# Speedometer_PCB_schematic.net
KiCad netlist of a schematic drawn in Altium Designer
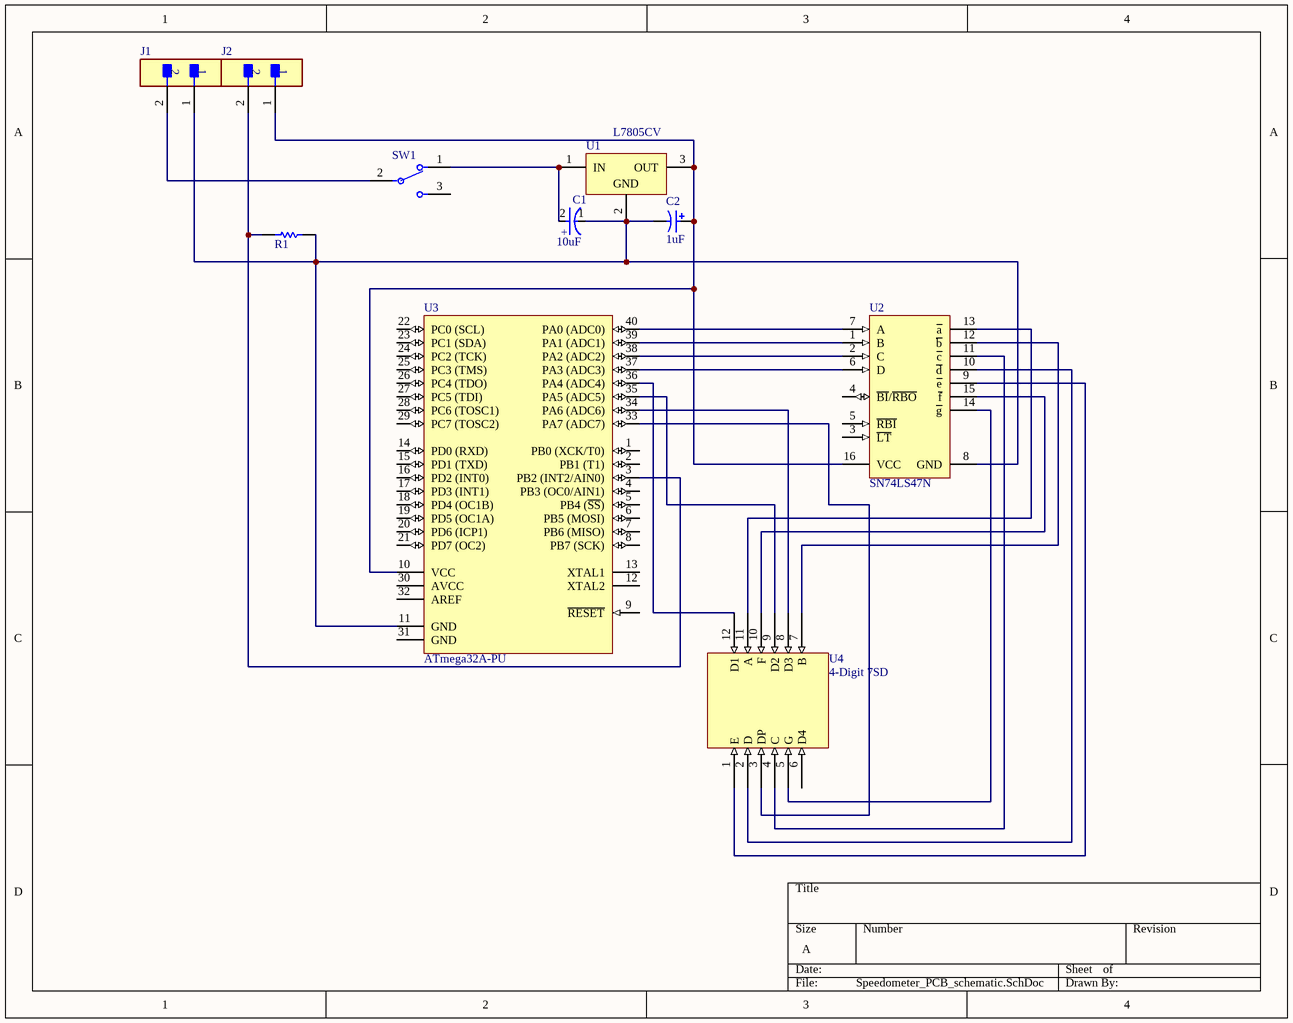
[diagram p0: Speedometer_PCB_schematic.SchDoc]

(export (version "E")
  (design (tool "Eeschema 10.0.6"))
  (components
    (comp (ref "C1")
      (value "ECA2AM100")
      (footprint "FP-RAD-TH-D_5_0_5-L_11_1-MFG")
      (description "Aluminum Electrolytic Capacitors (Radial Lead Type) 10uF ±20% 100V")
      (fields
        (field (name "CAPACITANCE") "10uF")
        (field (name "VOLTAGE") "100V")
        (field (name "TOLERANCE") "20%")
      )
      (libsource (lib "Altium Content Vault") (part "a00bbbee19879c290e62620ae7e47b1"))
    )
    (comp (ref "C2")
      (value "1uF")
      (footprint "CAPPR55-200-1100X500X1200")
      (description "Aluminum Electrolytic Capacitor, 1 uF, +/- 20%, 50 V, -55 to 105 degC, 2-Pin THD, RoHS, Bulk")
      (libsource (lib "Altium Content Vault") (part "CAP-P-2"))
    )
    (comp (ref "J1")
      (value "M20-9990246")
      (footprint "FP-M20-9990246-MFG")
      (description "Connector Header Through Hole 2 position 0.100\" (2.54mm)")
      (fields (field (name "OCTOPART") "https://octopart.com/m20-9990246-harwin-2590635"))
      (libsource (lib "Altium Content Vault") (part "3bc925449376181038e59eaffc5286c"))
    )
    (comp (ref "J2")
      (value "M20-9990246")
      (footprint "FP-M20-9990246-MFG")
      (description "Connector Header Through Hole 2 position 0.100\" (2.54mm)")
      (fields (field (name "OCTOPART") "https://octopart.com/m20-9990246-harwin-2590635"))
      (libsource (lib "Altium Content Vault") (part "3bc925449376181038e59eaffc5286c"))
    )
    (comp (ref "R1")
      (value "MFR-25FBF52-1K")
      (footprint "RESA60-630X240")
      (description "Axial Resistor, 1 KOhm, +/- 1%, 250 mW, -55 to 155 degC, 2-Pin THD, RoHS, Bulk")
      (fields (field (name "TOLERANCE") "1%"))
      (libsource (lib "Altium Content Vault") (part "RES-2"))
    )
    (comp (ref "SW1")
      (value "1101M2S3CQE2")
      (footprint "FP-1101M2S3CQE2-MFG")
      (description "SWITCH SLIDE SPDT 6A 120V")
      (libsource (lib "Altium Content Vault") (part "7fcaa069a19c2acd609832313418d7c"))
    )
    (comp (ref "U1")
      (value "L7805CV")
      (footprint "TO220")
      (description "Positive Voltage Regulator, 5V, 3-Pin TO-220")
      (libsource (lib "Altium Content Vault") (part "PM-REG-L4940-SIL3"))
    )
    (comp (ref "U2")
      (value "SN74LS47N")
      (footprint "N0016A")
      (description "BCD-to-7-Segment Decoder / Driver, 4.75 to 5.25 V, 0 to 70 degC, 16-pin DIP (N16), Pb-Free (RoHS)")
      (fields (field (name "MANUFACTURER") "Texas Instruments"))
      (libsource (lib "Altium Content Vault") (part "TI-SNX4XX247-16"))
    )
    (comp (ref "U3")
      (value "ATmega32A-PU")
      (footprint "40P6")
      (libsource (lib "Altium Content Vault") (part "MC-8B-AT16A-IL40"))
    )
    (comp (ref "U4")
      (value "4-Digit 7SD")
      (footprint "4-Digit 7SD")
      (libsource (lib "Speedometer") (part "4-Digit 7SD"))
    )
  )
  (nets
    (net (code "1") (name "Net-(C1-A)") (class "Default")
      (node (ref "C1") (pin "2") (pinfunction "A_2") (pintype "passive"))
      (node (ref "SW1") (pin "1") (pinfunction "1_1") (pintype "passive"))
      (node (ref "U1") (pin "1") (pinfunction "IN_1") (pintype "power_in"))
    )
    (net (code "2") (name "Net-(C1-C)") (class "Default")
      (node (ref "C1") (pin "1") (pinfunction "C_1") (pintype "passive"))
      (node (ref "C2") (pin "2") (pinfunction "2_2") (pintype "passive"))
      (node (ref "J1") (pin "1") (pinfunction "1_1") (pintype "passive"))
      (node (ref "R1") (pin "2") (pinfunction "2_2") (pintype "passive"))
      (node (ref "U1") (pin "2") (pinfunction "GND_2") (pintype "power_in"))
      (node (ref "U2") (pin "8") (pinfunction "GND_8") (pintype "power_in"))
      (node (ref "U3") (pin "11") (pinfunction "GND_11") (pintype "power_in"))
    )
    (net (code "3") (name "Net-(SW1-COMM)") (class "Default")
      (node (ref "J1") (pin "2") (pinfunction "2_2") (pintype "passive"))
      (node (ref "SW1") (pin "2") (pinfunction "COMM_2") (pintype "passive"))
    )
    (net (code "4") (name "Net-(U1-OUT)") (class "Default")
      (node (ref "C2") (pin "1") (pinfunction "1_1") (pintype "passive"))
      (node (ref "J2") (pin "1") (pinfunction "1_1") (pintype "passive"))
      (node (ref "U1") (pin "3") (pinfunction "OUT_3") (pintype "power_in"))
      (node (ref "U2") (pin "16") (pinfunction "VCC_16") (pintype "power_in"))
      (node (ref "U3") (pin "10") (pinfunction "VCC_10") (pintype "power_in"))
    )
    (net (code "5") (name "Net-(U2-A)") (class "Default")
      (node (ref "U2") (pin "7") (pinfunction "A_7") (pintype "input"))
      (node (ref "U3") (pin "40") (pinfunction "PA0_(ADC0)_40") (pintype "bidirectional"))
    )
    (net (code "6") (name "Net-(U2-B)") (class "Default")
      (node (ref "U2") (pin "1") (pinfunction "B_1") (pintype "input"))
      (node (ref "U3") (pin "39") (pinfunction "PA1_(ADC1)_39") (pintype "bidirectional"))
    )
    (net (code "7") (name "Net-(U2-C)") (class "Default")
      (node (ref "U2") (pin "2") (pinfunction "C_2") (pintype "input"))
      (node (ref "U3") (pin "38") (pinfunction "PA2_(ADC2)_38") (pintype "bidirectional"))
    )
    (net (code "8") (name "Net-(U2-D)") (class "Default")
      (node (ref "U2") (pin "6") (pinfunction "D_6") (pintype "input"))
      (node (ref "U3") (pin "37") (pinfunction "PA3_(ADC3)_37") (pintype "bidirectional"))
    )
    (net (code "9") (name "Net-(U2-~{a})") (class "Default")
      (node (ref "U2") (pin "13") (pinfunction "~{a}_13") (pintype "open_collector"))
      (node (ref "U4") (pin "11") (pinfunction "A_11") (pintype "input"))
    )
    (net (code "10") (name "Net-(U2-~{b})") (class "Default")
      (node (ref "U2") (pin "12") (pinfunction "~{b}_12") (pintype "open_collector"))
      (node (ref "U4") (pin "7") (pinfunction "B_7") (pintype "input"))
    )
    (net (code "11") (name "Net-(U2-~{c})") (class "Default")
      (node (ref "U2") (pin "11") (pinfunction "~{c}_11") (pintype "open_collector"))
      (node (ref "U4") (pin "4") (pinfunction "C_4") (pintype "input"))
    )
    (net (code "12") (name "Net-(U2-~{d})") (class "Default")
      (node (ref "U2") (pin "10") (pinfunction "~{d}_10") (pintype "open_collector"))
      (node (ref "U4") (pin "2") (pinfunction "D_2") (pintype "input"))
    )
    (net (code "13") (name "Net-(U2-~{e})") (class "Default")
      (node (ref "U2") (pin "9") (pinfunction "~{e}_9") (pintype "open_collector"))
      (node (ref "U4") (pin "1") (pinfunction "E_1") (pintype "input"))
    )
    (net (code "14") (name "Net-(U2-~{f})") (class "Default")
      (node (ref "U2") (pin "15") (pinfunction "~{f}_15") (pintype "open_collector"))
      (node (ref "U4") (pin "10") (pinfunction "F_10") (pintype "input"))
    )
    (net (code "15") (name "Net-(U2-~{g})") (class "Default")
      (node (ref "U2") (pin "14") (pinfunction "~{g}_14") (pintype "open_collector"))
      (node (ref "U4") (pin "5") (pinfunction "G_5") (pintype "input"))
    )
    (net (code "16") (name "Net-(U3-PA4_(ADC4))") (class "Default")
      (node (ref "U3") (pin "36") (pinfunction "PA4_(ADC4)_36") (pintype "bidirectional"))
      (node (ref "U4") (pin "12") (pinfunction "D1_12") (pintype "input"))
    )
    (net (code "17") (name "Net-(U3-PA5_(ADC5))") (class "Default")
      (node (ref "U3") (pin "35") (pinfunction "PA5_(ADC5)_35") (pintype "bidirectional"))
      (node (ref "U4") (pin "9") (pinfunction "D2_9") (pintype "input"))
    )
    (net (code "18") (name "Net-(U3-PA6_(ADC6))") (class "Default")
      (node (ref "U3") (pin "34") (pinfunction "PA6_(ADC6)_34") (pintype "bidirectional"))
      (node (ref "U4") (pin "8") (pinfunction "D3_8") (pintype "input"))
    )
    (net (code "19") (name "Net-(U3-PA7_(ADC7))") (class "Default")
      (node (ref "U3") (pin "33") (pinfunction "PA7_(ADC7)_33") (pintype "bidirectional"))
      (node (ref "U4") (pin "3") (pinfunction "DP_3") (pintype "input"))
    )
    (net (code "20") (name "Net-(U3-PB2_(INT2{slash}AIN0))") (class "Default")
      (node (ref "J2") (pin "2") (pinfunction "2_2") (pintype "passive"))
      (node (ref "R1") (pin "1") (pinfunction "1_1") (pintype "passive"))
      (node (ref "U3") (pin "3") (pinfunction "PB2_(INT2/AIN0)_3") (pintype "bidirectional"))
    )
    (net (code "21") (name "unconnected-(SW1-Pad3)") (class "Default")
      (node (ref "SW1") (pin "3") (pinfunction "3_3") (pintype "passive"))
    )
    (net (code "22") (name "unconnected-(U2-~{BI}{slash}~{RBO}-Pad4)") (class "Default")
      (node (ref "U2") (pin "4") (pinfunction "~{BI}/~{RBO}_4") (pintype "bidirectional"))
    )
    (net (code "23") (name "unconnected-(U2-~{LT}-Pad3)") (class "Default")
      (node (ref "U2") (pin "3") (pinfunction "~{LT}_3") (pintype "input"))
    )
    (net (code "24") (name "unconnected-(U2-~{RBI}-Pad5)") (class "Default")
      (node (ref "U2") (pin "5") (pinfunction "~{RBI}_5") (pintype "input"))
    )
    (net (code "25") (name "unconnected-(U3-AREF-Pad32)") (class "Default")
      (node (ref "U3") (pin "32") (pinfunction "AREF_32") (pintype "power_in"))
    )
    (net (code "26") (name "unconnected-(U3-AVCC-Pad30)") (class "Default")
      (node (ref "U3") (pin "30") (pinfunction "AVCC_30") (pintype "power_in"))
    )
    (net (code "27") (name "unconnected-(U3-GND-Pad31)") (class "Default")
      (node (ref "U3") (pin "31") (pinfunction "GND_31") (pintype "power_in"))
    )
    (net (code "28") (name "unconnected-(U3-PB0_(XCK{slash}T0)-Pad1)") (class "Default")
      (node (ref "U3") (pin "1") (pinfunction "PB0_(XCK/T0)_1") (pintype "bidirectional"))
    )
    (net (code "29") (name "unconnected-(U3-PB1_(T1)-Pad2)") (class "Default")
      (node (ref "U3") (pin "2") (pinfunction "PB1_(T1)_2") (pintype "bidirectional"))
    )
    (net (code "30") (name "unconnected-(U3-PB3_(OC0{slash}AIN1)-Pad4)") (class "Default")
      (node (ref "U3") (pin "4") (pinfunction "PB3_(OC0/AIN1)_4") (pintype "bidirectional"))
    )
    (net (code "31") (name "unconnected-(U3-PB4_(~{SS})-Pad5)") (class "Default")
      (node (ref "U3") (pin "5") (pinfunction "PB4_(~{SS})_5") (pintype "bidirectional"))
    )
    (net (code "32") (name "unconnected-(U3-PB5_(MOSI)-Pad6)") (class "Default")
      (node (ref "U3") (pin "6") (pinfunction "PB5_(MOSI)_6") (pintype "bidirectional"))
    )
    (net (code "33") (name "unconnected-(U3-PB6_(MISO)-Pad7)") (class "Default")
      (node (ref "U3") (pin "7") (pinfunction "PB6_(MISO)_7") (pintype "bidirectional"))
    )
    (net (code "34") (name "unconnected-(U3-PB7_(SCK)-Pad8)") (class "Default")
      (node (ref "U3") (pin "8") (pinfunction "PB7_(SCK)_8") (pintype "bidirectional"))
    )
    (net (code "35") (name "unconnected-(U3-PC0_(SCL)-Pad22)") (class "Default")
      (node (ref "U3") (pin "22") (pinfunction "PC0_(SCL)_22") (pintype "bidirectional"))
    )
    (net (code "36") (name "unconnected-(U3-PC1_(SDA)-Pad23)") (class "Default")
      (node (ref "U3") (pin "23") (pinfunction "PC1_(SDA)_23") (pintype "bidirectional"))
    )
    (net (code "37") (name "unconnected-(U3-PC2_(TCK)-Pad24)") (class "Default")
      (node (ref "U3") (pin "24") (pinfunction "PC2_(TCK)_24") (pintype "bidirectional"))
    )
    (net (code "38") (name "unconnected-(U3-PC3_(TMS)-Pad25)") (class "Default")
      (node (ref "U3") (pin "25") (pinfunction "PC3_(TMS)_25") (pintype "bidirectional"))
    )
    (net (code "39") (name "unconnected-(U3-PC4_(TDO)-Pad26)") (class "Default")
      (node (ref "U3") (pin "26") (pinfunction "PC4_(TDO)_26") (pintype "bidirectional"))
    )
    (net (code "40") (name "unconnected-(U3-PC5_(TDI)-Pad27)") (class "Default")
      (node (ref "U3") (pin "27") (pinfunction "PC5_(TDI)_27") (pintype "bidirectional"))
    )
    (net (code "41") (name "unconnected-(U3-PC6_(TOSC1)-Pad28)") (class "Default")
      (node (ref "U3") (pin "28") (pinfunction "PC6_(TOSC1)_28") (pintype "bidirectional"))
    )
    (net (code "42") (name "unconnected-(U3-PC7_(TOSC2)-Pad29)") (class "Default")
      (node (ref "U3") (pin "29") (pinfunction "PC7_(TOSC2)_29") (pintype "bidirectional"))
    )
    (net (code "43") (name "unconnected-(U3-PD0_(RXD)-Pad14)") (class "Default")
      (node (ref "U3") (pin "14") (pinfunction "PD0_(RXD)_14") (pintype "bidirectional"))
    )
    (net (code "44") (name "unconnected-(U3-PD1_(TXD)-Pad15)") (class "Default")
      (node (ref "U3") (pin "15") (pinfunction "PD1_(TXD)_15") (pintype "bidirectional"))
    )
    (net (code "45") (name "unconnected-(U3-PD2_(INT0)-Pad16)") (class "Default")
      (node (ref "U3") (pin "16") (pinfunction "PD2_(INT0)_16") (pintype "bidirectional"))
    )
    (net (code "46") (name "unconnected-(U3-PD3_(INT1)-Pad17)") (class "Default")
      (node (ref "U3") (pin "17") (pinfunction "PD3_(INT1)_17") (pintype "bidirectional"))
    )
    (net (code "47") (name "unconnected-(U3-PD4_(OC1B)-Pad18)") (class "Default")
      (node (ref "U3") (pin "18") (pinfunction "PD4_(OC1B)_18") (pintype "bidirectional"))
    )
    (net (code "48") (name "unconnected-(U3-PD5_(OC1A)-Pad19)") (class "Default")
      (node (ref "U3") (pin "19") (pinfunction "PD5_(OC1A)_19") (pintype "bidirectional"))
    )
    (net (code "49") (name "unconnected-(U3-PD6_(ICP1)-Pad20)") (class "Default")
      (node (ref "U3") (pin "20") (pinfunction "PD6_(ICP1)_20") (pintype "bidirectional"))
    )
    (net (code "50") (name "unconnected-(U3-PD7_(OC2)-Pad21)") (class "Default")
      (node (ref "U3") (pin "21") (pinfunction "PD7_(OC2)_21") (pintype "bidirectional"))
    )
    (net (code "51") (name "unconnected-(U3-XTAL1-Pad13)") (class "Default")
      (node (ref "U3") (pin "13") (pinfunction "XTAL1_13") (pintype "passive"))
    )
    (net (code "52") (name "unconnected-(U3-XTAL2-Pad12)") (class "Default")
      (node (ref "U3") (pin "12") (pinfunction "XTAL2_12") (pintype "passive"))
    )
    (net (code "53") (name "unconnected-(U3-~{RESET}-Pad9)") (class "Default")
      (node (ref "U3") (pin "9") (pinfunction "~{RESET}_9") (pintype "input"))
    )
    (net (code "54") (name "unconnected-(U4-D4-Pad6)") (class "Default")
      (node (ref "U4") (pin "6") (pinfunction "D4_6") (pintype "input"))
    )
  )
)
